# eMMCChip.net
KiCad netlist of a schematic drawn in Altium Designer
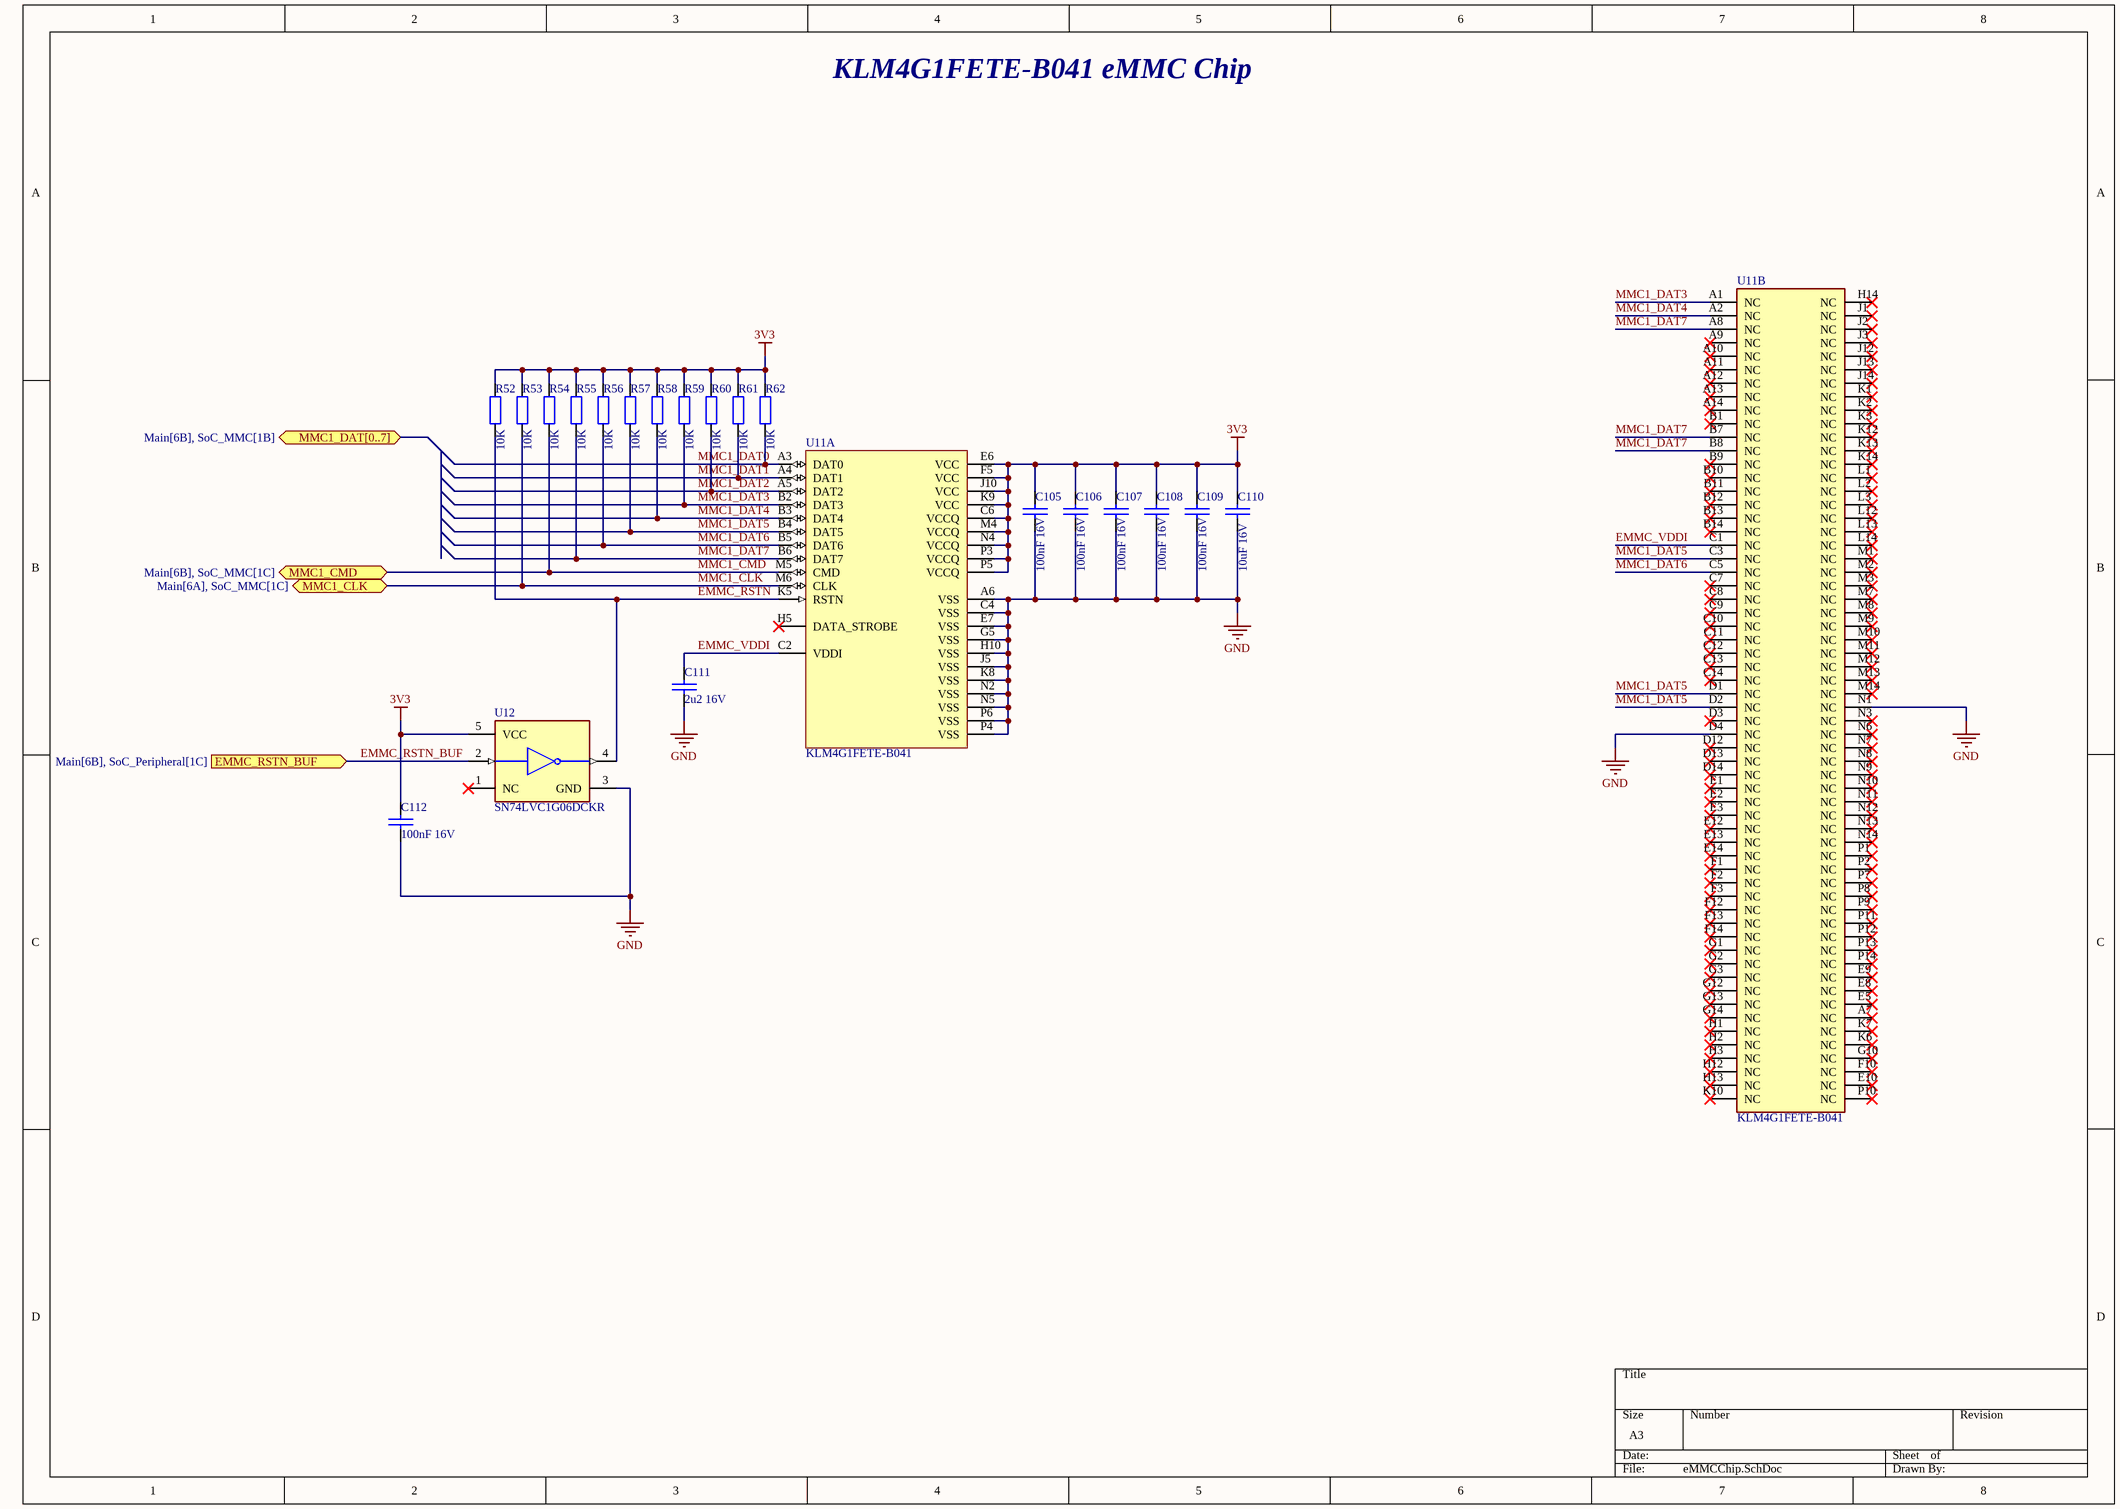
[diagram p0: eMMCChip.SchDoc]

(export (version "E")
  (design (tool "Eeschema 10.0.6"))
  (components
    (comp (ref "C105")
      (value "100nF 16V")
      (footprint "C_0402")
      (description "Capacitor 0402 SMD")
      (libsource (lib "tor1kkLib") (part "C_0402"))
    )
    (comp (ref "C106")
      (value "100nF 16V")
      (footprint "C_0402")
      (description "Capacitor 0402 SMD")
      (libsource (lib "tor1kkLib") (part "C_0402"))
    )
    (comp (ref "C107")
      (value "100nF 16V")
      (footprint "C_0402")
      (description "Capacitor 0402 SMD")
      (libsource (lib "tor1kkLib") (part "C_0402"))
    )
    (comp (ref "C108")
      (value "100nF 16V")
      (footprint "C_0402")
      (description "Capacitor 0402 SMD")
      (libsource (lib "tor1kkLib") (part "C_0402"))
    )
    (comp (ref "C109")
      (value "100nF 16V")
      (footprint "C_0402")
      (description "Capacitor 0402 SMD")
      (libsource (lib "tor1kkLib") (part "C_0402"))
    )
    (comp (ref "C110")
      (value "10uF 16V")
      (footprint "C_0603")
      (description "Capacitor 0603 SMD")
      (libsource (lib "tor1kkLib") (part "C_0603"))
    )
    (comp (ref "C111")
      (value "2u2 16V")
      (footprint "C_0402")
      (description "Capacitor 0402 SMD")
      (libsource (lib "tor1kkLib") (part "C_0402"))
    )
    (comp (ref "C112")
      (value "100nF 16V")
      (footprint "C_0402")
      (description "Capacitor 0402 SMD")
      (libsource (lib "tor1kkLib") (part "C_0402"))
    )
    (comp (ref "R52")
      (value "10K")
      (footprint "R_0402")
      (description "Resistor 0402 SMD")
      (libsource (lib "tor1kkLib") (part "R_0402"))
    )
    (comp (ref "R53")
      (value "10K")
      (footprint "R_0402")
      (description "Resistor 0402 SMD")
      (libsource (lib "tor1kkLib") (part "R_0402"))
    )
    (comp (ref "R54")
      (value "10K")
      (footprint "R_0402")
      (description "Resistor 0402 SMD")
      (libsource (lib "tor1kkLib") (part "R_0402"))
    )
    (comp (ref "R55")
      (value "10K")
      (footprint "R_0402")
      (description "Resistor 0402 SMD")
      (libsource (lib "tor1kkLib") (part "R_0402"))
    )
    (comp (ref "R56")
      (value "10K")
      (footprint "R_0402")
      (description "Resistor 0402 SMD")
      (libsource (lib "tor1kkLib") (part "R_0402"))
    )
    (comp (ref "R57")
      (value "10K")
      (footprint "R_0402")
      (description "Resistor 0402 SMD")
      (libsource (lib "tor1kkLib") (part "R_0402"))
    )
    (comp (ref "R58")
      (value "10K")
      (footprint "R_0402")
      (description "Resistor 0402 SMD")
      (libsource (lib "tor1kkLib") (part "R_0402"))
    )
    (comp (ref "R59")
      (value "10K")
      (footprint "R_0402")
      (description "Resistor 0402 SMD")
      (libsource (lib "tor1kkLib") (part "R_0402"))
    )
    (comp (ref "R60")
      (value "10K")
      (footprint "R_0402")
      (description "Resistor 0402 SMD")
      (libsource (lib "tor1kkLib") (part "R_0402"))
    )
    (comp (ref "R61")
      (value "10K")
      (footprint "R_0402")
      (description "Resistor 0402 SMD")
      (libsource (lib "tor1kkLib") (part "R_0402"))
    )
    (comp (ref "R62")
      (value "10K")
      (footprint "R_0402")
      (description "Resistor 0402 SMD")
      (libsource (lib "tor1kkLib") (part "R_0402"))
    )
    (comp (ref "U11")
      (value "KLM4G1FETE-B041")
      (footprint "BGA153C50P14X14_1100X1000X80")
      (description "4GB 300/19 MB/s eMMC 5.1 FBGA-153(10x11) eMMC ROHS")
      (fields (field (name "MANUFACTURER") "Samsung"))
      (libsource (lib "tor1kkLib") (part "KLM4G1FETE-B041"))
    )
    (comp (ref "U12")
      (value "SN74LVC1G06DCKR")
      (footprint "FP-DCK0005A-MFG")
      (description "IC BUFFER INVERT 5.5V SC70-5")
      (fields
        (field (name "MANUFACTURER") "Texas Instruments")
        (field (name "OCTOPART") "https://octopart.com/sn74lvc1g06dckr-texas+instruments-465505")
      )
      (libsource (lib "Altium Content Vault") (part "3c7ee7ed174875a000d335133ab233a"))
    )
  )
  (nets
    (net (code "1") (name "/EMMC_RSTN") (class "Default")
      (node (ref "R52") (pin "1") (pintype "passive"))
      (node (ref "U11") (pin "K5") (pinfunction "RSTN_K5") (pintype "input"))
      (node (ref "U12") (pin "4") (pinfunction "Y_4") (pintype "output"))
    )
    (net (code "2") (name "/EMMC_RSTN_BUF") (class "Default")
      (node (ref "U12") (pin "2") (pinfunction "A_2") (pintype "input"))
    )
    (net (code "3") (name "/EMMC_VDDI") (class "Default")
      (node (ref "C111") (pin "1") (pintype "passive"))
      (node (ref "U11") (pin "C1") (pinfunction "NC_C1") (pintype "passive"))
      (node (ref "U11") (pin "C2") (pinfunction "VDDI_C2") (pintype "passive"))
    )
    (net (code "4") (name "/MMC1_CLK") (class "Default")
      (node (ref "R53") (pin "1") (pintype "passive"))
      (node (ref "U11") (pin "M6") (pinfunction "CLK_M6") (pintype "bidirectional"))
    )
    (net (code "5") (name "/MMC1_CMD") (class "Default")
      (node (ref "R54") (pin "1") (pintype "passive"))
      (node (ref "U11") (pin "M5") (pinfunction "CMD_M5") (pintype "bidirectional"))
    )
    (net (code "6") (name "/MMC1_DAT0") (class "Default")
      (node (ref "R62") (pin "1") (pintype "passive"))
      (node (ref "U11") (pin "A3") (pinfunction "DAT0_A3") (pintype "bidirectional"))
    )
    (net (code "7") (name "/MMC1_DAT1") (class "Default")
      (node (ref "R61") (pin "1") (pintype "passive"))
      (node (ref "U11") (pin "A4") (pinfunction "DAT1_A4") (pintype "bidirectional"))
    )
    (net (code "8") (name "/MMC1_DAT2") (class "Default")
      (node (ref "R60") (pin "1") (pintype "passive"))
      (node (ref "U11") (pin "A5") (pinfunction "DAT2_A5") (pintype "bidirectional"))
    )
    (net (code "9") (name "/MMC1_DAT3") (class "Default")
      (node (ref "R59") (pin "1") (pintype "passive"))
      (node (ref "U11") (pin "A1") (pinfunction "NC_A1") (pintype "passive"))
      (node (ref "U11") (pin "B2") (pinfunction "DAT3_B2") (pintype "bidirectional"))
    )
    (net (code "10") (name "/MMC1_DAT4") (class "Default")
      (node (ref "R58") (pin "1") (pintype "passive"))
      (node (ref "U11") (pin "A2") (pinfunction "NC_A2") (pintype "passive"))
      (node (ref "U11") (pin "B3") (pinfunction "DAT4_B3") (pintype "bidirectional"))
    )
    (net (code "11") (name "/MMC1_DAT5") (class "Default")
      (node (ref "R57") (pin "1") (pintype "passive"))
      (node (ref "U11") (pin "B4") (pinfunction "DAT5_B4") (pintype "bidirectional"))
      (node (ref "U11") (pin "C3") (pinfunction "NC_C3") (pintype "passive"))
      (node (ref "U11") (pin "D1") (pinfunction "NC_D1") (pintype "passive"))
      (node (ref "U11") (pin "D2") (pinfunction "NC_D2") (pintype "passive"))
    )
    (net (code "12") (name "/MMC1_DAT6") (class "Default")
      (node (ref "R56") (pin "1") (pintype "passive"))
      (node (ref "U11") (pin "B5") (pinfunction "DAT6_B5") (pintype "bidirectional"))
      (node (ref "U11") (pin "C5") (pinfunction "NC_C5") (pintype "passive"))
    )
    (net (code "13") (name "/MMC1_DAT7") (class "Default")
      (node (ref "R55") (pin "1") (pintype "passive"))
      (node (ref "U11") (pin "A8") (pinfunction "NC_A8") (pintype "passive"))
      (node (ref "U11") (pin "B6") (pinfunction "DAT7_B6") (pintype "bidirectional"))
      (node (ref "U11") (pin "B7") (pinfunction "NC_B7") (pintype "passive"))
      (node (ref "U11") (pin "B8") (pinfunction "NC_B8") (pintype "passive"))
    )
    (net (code "15") (name "3V3") (class "Default")
      (node (ref "C105") (pin "1") (pintype "passive"))
      (node (ref "C106") (pin "1") (pintype "passive"))
      (node (ref "C107") (pin "1") (pintype "passive"))
      (node (ref "C108") (pin "1") (pintype "passive"))
      (node (ref "C109") (pin "1") (pintype "passive"))
      (node (ref "C110") (pin "1") (pintype "passive"))
      (node (ref "C112") (pin "1") (pintype "passive"))
      (node (ref "R52") (pin "2") (pintype "passive"))
      (node (ref "R53") (pin "2") (pintype "passive"))
      (node (ref "R54") (pin "2") (pintype "passive"))
      (node (ref "R55") (pin "2") (pintype "passive"))
      (node (ref "R56") (pin "2") (pintype "passive"))
      (node (ref "R57") (pin "2") (pintype "passive"))
      (node (ref "R58") (pin "2") (pintype "passive"))
      (node (ref "R59") (pin "2") (pintype "passive"))
      (node (ref "R60") (pin "2") (pintype "passive"))
      (node (ref "R61") (pin "2") (pintype "passive"))
      (node (ref "R62") (pin "2") (pintype "passive"))
      (node (ref "U11") (pin "C6") (pinfunction "VCCQ_C6") (pintype "passive"))
      (node (ref "U11") (pin "E6") (pinfunction "VCC_E6") (pintype "passive"))
      (node (ref "U11") (pin "F5") (pinfunction "VCC_F5") (pintype "passive"))
      (node (ref "U11") (pin "J10") (pinfunction "VCC_J10") (pintype "passive"))
      (node (ref "U11") (pin "K9") (pinfunction "VCC_K9") (pintype "passive"))
      (node (ref "U11") (pin "M4") (pinfunction "VCCQ_M4") (pintype "passive"))
      (node (ref "U11") (pin "N4") (pinfunction "VCCQ_N4") (pintype "passive"))
      (node (ref "U11") (pin "P3") (pinfunction "VCCQ_P3") (pintype "passive"))
      (node (ref "U11") (pin "P5") (pinfunction "VCCQ_P5") (pintype "passive"))
      (node (ref "U12") (pin "5") (pinfunction "VCC_5") (pintype "power_in"))
    )
    (net (code "16") (name "GND") (class "Default")
      (node (ref "C105") (pin "2") (pintype "passive"))
      (node (ref "C106") (pin "2") (pintype "passive"))
      (node (ref "C107") (pin "2") (pintype "passive"))
      (node (ref "C108") (pin "2") (pintype "passive"))
      (node (ref "C109") (pin "2") (pintype "passive"))
      (node (ref "C110") (pin "2") (pintype "passive"))
      (node (ref "C111") (pin "2") (pintype "passive"))
      (node (ref "C112") (pin "2") (pintype "passive"))
      (node (ref "U11") (pin "A6") (pinfunction "VSS_A6") (pintype "passive"))
      (node (ref "U11") (pin "C4") (pinfunction "VSS_C4") (pintype "passive"))
      (node (ref "U11") (pin "D4") (pinfunction "NC_D4") (pintype "passive"))
      (node (ref "U11") (pin "E7") (pinfunction "VSS_E7") (pintype "passive"))
      (node (ref "U11") (pin "G5") (pinfunction "VSS_G5") (pintype "passive"))
      (node (ref "U11") (pin "H10") (pinfunction "VSS_H10") (pintype "passive"))
      (node (ref "U11") (pin "J5") (pinfunction "VSS_J5") (pintype "passive"))
      (node (ref "U11") (pin "K8") (pinfunction "VSS_K8") (pintype "passive"))
      (node (ref "U11") (pin "N1") (pinfunction "NC_N1") (pintype "passive"))
      (node (ref "U11") (pin "N2") (pinfunction "VSS_N2") (pintype "passive"))
      (node (ref "U11") (pin "N5") (pinfunction "VSS_N5") (pintype "passive"))
      (node (ref "U11") (pin "P4") (pinfunction "VSS_P4") (pintype "passive"))
      (node (ref "U11") (pin "P6") (pinfunction "VSS_P6") (pintype "passive"))
      (node (ref "U12") (pin "3") (pinfunction "GND_3") (pintype "power_in"))
    )
    (net (code "17") (name "unconnected-(U11A-DATA_STROBE-PadH5)") (class "Default")
      (node (ref "U11") (pin "H5") (pinfunction "DATA_STROBE_H5") (pintype "passive+no_connect"))
    )
    (net (code "18") (name "unconnected-(U11B-NC-PadA7)") (class "Default")
      (node (ref "U11") (pin "A7") (pinfunction "NC_A7") (pintype "passive+no_connect"))
    )
    (net (code "19") (name "unconnected-(U11B-NC-PadA9)") (class "Default")
      (node (ref "U11") (pin "A9") (pinfunction "NC_A9") (pintype "passive+no_connect"))
    )
    (net (code "20") (name "unconnected-(U11B-NC-PadA10)") (class "Default")
      (node (ref "U11") (pin "A10") (pinfunction "NC_A10") (pintype "passive+no_connect"))
    )
    (net (code "21") (name "unconnected-(U11B-NC-PadA11)") (class "Default")
      (node (ref "U11") (pin "A11") (pinfunction "NC_A11") (pintype "passive+no_connect"))
    )
    (net (code "22") (name "unconnected-(U11B-NC-PadA12)") (class "Default")
      (node (ref "U11") (pin "A12") (pinfunction "NC_A12") (pintype "passive+no_connect"))
    )
    (net (code "23") (name "unconnected-(U11B-NC-PadA13)") (class "Default")
      (node (ref "U11") (pin "A13") (pinfunction "NC_A13") (pintype "passive+no_connect"))
    )
    (net (code "24") (name "unconnected-(U11B-NC-PadA14)") (class "Default")
      (node (ref "U11") (pin "A14") (pinfunction "NC_A14") (pintype "passive+no_connect"))
    )
    (net (code "25") (name "unconnected-(U11B-NC-PadB1)") (class "Default")
      (node (ref "U11") (pin "B1") (pinfunction "NC_B1") (pintype "passive+no_connect"))
    )
    (net (code "26") (name "unconnected-(U11B-NC-PadB9)") (class "Default")
      (node (ref "U11") (pin "B9") (pinfunction "NC_B9") (pintype "passive+no_connect"))
    )
    (net (code "27") (name "unconnected-(U11B-NC-PadB10)") (class "Default")
      (node (ref "U11") (pin "B10") (pinfunction "NC_B10") (pintype "passive+no_connect"))
    )
    (net (code "28") (name "unconnected-(U11B-NC-PadB11)") (class "Default")
      (node (ref "U11") (pin "B11") (pinfunction "NC_B11") (pintype "passive+no_connect"))
    )
    (net (code "29") (name "unconnected-(U11B-NC-PadB12)") (class "Default")
      (node (ref "U11") (pin "B12") (pinfunction "NC_B12") (pintype "passive+no_connect"))
    )
    (net (code "30") (name "unconnected-(U11B-NC-PadB13)") (class "Default")
      (node (ref "U11") (pin "B13") (pinfunction "NC_B13") (pintype "passive+no_connect"))
    )
    (net (code "31") (name "unconnected-(U11B-NC-PadB14)") (class "Default")
      (node (ref "U11") (pin "B14") (pinfunction "NC_B14") (pintype "passive+no_connect"))
    )
    (net (code "32") (name "unconnected-(U11B-NC-PadC7)") (class "Default")
      (node (ref "U11") (pin "C7") (pinfunction "NC_C7") (pintype "passive+no_connect"))
    )
    (net (code "33") (name "unconnected-(U11B-NC-PadC8)") (class "Default")
      (node (ref "U11") (pin "C8") (pinfunction "NC_C8") (pintype "passive+no_connect"))
    )
    (net (code "34") (name "unconnected-(U11B-NC-PadC9)") (class "Default")
      (node (ref "U11") (pin "C9") (pinfunction "NC_C9") (pintype "passive+no_connect"))
    )
    (net (code "35") (name "unconnected-(U11B-NC-PadC10)") (class "Default")
      (node (ref "U11") (pin "C10") (pinfunction "NC_C10") (pintype "passive+no_connect"))
    )
    (net (code "36") (name "unconnected-(U11B-NC-PadC11)") (class "Default")
      (node (ref "U11") (pin "C11") (pinfunction "NC_C11") (pintype "passive+no_connect"))
    )
    (net (code "37") (name "unconnected-(U11B-NC-PadC12)") (class "Default")
      (node (ref "U11") (pin "C12") (pinfunction "NC_C12") (pintype "passive+no_connect"))
    )
    (net (code "38") (name "unconnected-(U11B-NC-PadC13)") (class "Default")
      (node (ref "U11") (pin "C13") (pinfunction "NC_C13") (pintype "passive+no_connect"))
    )
    (net (code "39") (name "unconnected-(U11B-NC-PadC14)") (class "Default")
      (node (ref "U11") (pin "C14") (pinfunction "NC_C14") (pintype "passive+no_connect"))
    )
    (net (code "40") (name "unconnected-(U11B-NC-PadD3)") (class "Default")
      (node (ref "U11") (pin "D3") (pinfunction "NC_D3") (pintype "passive+no_connect"))
    )
    (net (code "41") (name "unconnected-(U11B-NC-PadD12)") (class "Default")
      (node (ref "U11") (pin "D12") (pinfunction "NC_D12") (pintype "passive+no_connect"))
    )
    (net (code "42") (name "unconnected-(U11B-NC-PadD13)") (class "Default")
      (node (ref "U11") (pin "D13") (pinfunction "NC_D13") (pintype "passive+no_connect"))
    )
    (net (code "43") (name "unconnected-(U11B-NC-PadD14)") (class "Default")
      (node (ref "U11") (pin "D14") (pinfunction "NC_D14") (pintype "passive+no_connect"))
    )
    (net (code "44") (name "unconnected-(U11B-NC-PadE1)") (class "Default")
      (node (ref "U11") (pin "E1") (pinfunction "NC_E1") (pintype "passive+no_connect"))
    )
    (net (code "45") (name "unconnected-(U11B-NC-PadE2)") (class "Default")
      (node (ref "U11") (pin "E2") (pinfunction "NC_E2") (pintype "passive+no_connect"))
    )
    (net (code "46") (name "unconnected-(U11B-NC-PadE3)") (class "Default")
      (node (ref "U11") (pin "E3") (pinfunction "NC_E3") (pintype "passive+no_connect"))
    )
    (net (code "47") (name "unconnected-(U11B-NC-PadE5)") (class "Default")
      (node (ref "U11") (pin "E5") (pinfunction "NC_E5") (pintype "passive+no_connect"))
    )
    (net (code "48") (name "unconnected-(U11B-NC-PadE8)") (class "Default")
      (node (ref "U11") (pin "E8") (pinfunction "NC_E8") (pintype "passive+no_connect"))
    )
    (net (code "49") (name "unconnected-(U11B-NC-PadE9)") (class "Default")
      (node (ref "U11") (pin "E9") (pinfunction "NC_E9") (pintype "passive+no_connect"))
    )
    (net (code "50") (name "unconnected-(U11B-NC-PadE10)") (class "Default")
      (node (ref "U11") (pin "E10") (pinfunction "NC_E10") (pintype "passive+no_connect"))
    )
    (net (code "51") (name "unconnected-(U11B-NC-PadE12)") (class "Default")
      (node (ref "U11") (pin "E12") (pinfunction "NC_E12") (pintype "passive+no_connect"))
    )
    (net (code "52") (name "unconnected-(U11B-NC-PadE13)") (class "Default")
      (node (ref "U11") (pin "E13") (pinfunction "NC_E13") (pintype "passive+no_connect"))
    )
    (net (code "53") (name "unconnected-(U11B-NC-PadE14)") (class "Default")
      (node (ref "U11") (pin "E14") (pinfunction "NC_E14") (pintype "passive+no_connect"))
    )
    (net (code "54") (name "unconnected-(U11B-NC-PadF1)") (class "Default")
      (node (ref "U11") (pin "F1") (pinfunction "NC_F1") (pintype "passive+no_connect"))
    )
    (net (code "55") (name "unconnected-(U11B-NC-PadF2)") (class "Default")
      (node (ref "U11") (pin "F2") (pinfunction "NC_F2") (pintype "passive+no_connect"))
    )
    (net (code "56") (name "unconnected-(U11B-NC-PadF3)") (class "Default")
      (node (ref "U11") (pin "F3") (pinfunction "NC_F3") (pintype "passive+no_connect"))
    )
    (net (code "57") (name "unconnected-(U11B-NC-PadF10)") (class "Default")
      (node (ref "U11") (pin "F10") (pinfunction "NC_F10") (pintype "passive+no_connect"))
    )
    (net (code "58") (name "unconnected-(U11B-NC-PadF12)") (class "Default")
      (node (ref "U11") (pin "F12") (pinfunction "NC_F12") (pintype "passive+no_connect"))
    )
    (net (code "59") (name "unconnected-(U11B-NC-PadF13)") (class "Default")
      (node (ref "U11") (pin "F13") (pinfunction "NC_F13") (pintype "passive+no_connect"))
    )
    (net (code "60") (name "unconnected-(U11B-NC-PadF14)") (class "Default")
      (node (ref "U11") (pin "F14") (pinfunction "NC_F14") (pintype "passive+no_connect"))
    )
    (net (code "61") (name "unconnected-(U11B-NC-PadG1)") (class "Default")
      (node (ref "U11") (pin "G1") (pinfunction "NC_G1") (pintype "passive+no_connect"))
    )
    (net (code "62") (name "unconnected-(U11B-NC-PadG2)") (class "Default")
      (node (ref "U11") (pin "G2") (pinfunction "NC_G2") (pintype "passive+no_connect"))
    )
    (net (code "63") (name "unconnected-(U11B-NC-PadG3)") (class "Default")
      (node (ref "U11") (pin "G3") (pinfunction "NC_G3") (pintype "passive+no_connect"))
    )
    (net (code "64") (name "unconnected-(U11B-NC-PadG10)") (class "Default")
      (node (ref "U11") (pin "G10") (pinfunction "NC_G10") (pintype "passive+no_connect"))
    )
    (net (code "65") (name "unconnected-(U11B-NC-PadG12)") (class "Default")
      (node (ref "U11") (pin "G12") (pinfunction "NC_G12") (pintype "passive+no_connect"))
    )
    (net (code "66") (name "unconnected-(U11B-NC-PadG13)") (class "Default")
      (node (ref "U11") (pin "G13") (pinfunction "NC_G13") (pintype "passive+no_connect"))
    )
    (net (code "67") (name "unconnected-(U11B-NC-PadG14)") (class "Default")
      (node (ref "U11") (pin "G14") (pinfunction "NC_G14") (pintype "passive+no_connect"))
    )
    (net (code "68") (name "unconnected-(U11B-NC-PadH1)") (class "Default")
      (node (ref "U11") (pin "H1") (pinfunction "NC_H1") (pintype "passive+no_connect"))
    )
    (net (code "69") (name "unconnected-(U11B-NC-PadH2)") (class "Default")
      (node (ref "U11") (pin "H2") (pinfunction "NC_H2") (pintype "passive+no_connect"))
    )
    (net (code "70") (name "unconnected-(U11B-NC-PadH3)") (class "Default")
      (node (ref "U11") (pin "H3") (pinfunction "NC_H3") (pintype "passive+no_connect"))
    )
    (net (code "71") (name "unconnected-(U11B-NC-PadH12)") (class "Default")
      (node (ref "U11") (pin "H12") (pinfunction "NC_H12") (pintype "passive+no_connect"))
    )
    (net (code "72") (name "unconnected-(U11B-NC-PadH13)") (class "Default")
      (node (ref "U11") (pin "H13") (pinfunction "NC_H13") (pintype "passive+no_connect"))
    )
    (net (code "73") (name "unconnected-(U11B-NC-PadH14)") (class "Default")
      (node (ref "U11") (pin "H14") (pinfunction "NC_H14") (pintype "passive+no_connect"))
    )
    (net (code "74") (name "unconnected-(U11B-NC-PadJ1)") (class "Default")
      (node (ref "U11") (pin "J1") (pinfunction "NC_J1") (pintype "passive+no_connect"))
    )
    (net (code "75") (name "unconnected-(U11B-NC-PadJ2)") (class "Default")
      (node (ref "U11") (pin "J2") (pinfunction "NC_J2") (pintype "passive+no_connect"))
    )
    (net (code "76") (name "unconnected-(U11B-NC-PadJ3)") (class "Default")
      (node (ref "U11") (pin "J3") (pinfunction "NC_J3") (pintype "passive+no_connect"))
    )
    (net (code "77") (name "unconnected-(U11B-NC-PadJ12)") (class "Default")
      (node (ref "U11") (pin "J12") (pinfunction "NC_J12") (pintype "passive+no_connect"))
    )
    (net (code "78") (name "unconnected-(U11B-NC-PadJ13)") (class "Default")
      (node (ref "U11") (pin "J13") (pinfunction "NC_J13") (pintype "passive+no_connect"))
    )
    (net (code "79") (name "unconnected-(U11B-NC-PadJ14)") (class "Default")
      (node (ref "U11") (pin "J14") (pinfunction "NC_J14") (pintype "passive+no_connect"))
    )
    (net (code "80") (name "unconnected-(U11B-NC-PadK1)") (class "Default")
      (node (ref "U11") (pin "K1") (pinfunction "NC_K1") (pintype "passive+no_connect"))
    )
    (net (code "81") (name "unconnected-(U11B-NC-PadK2)") (class "Default")
      (node (ref "U11") (pin "K2") (pinfunction "NC_K2") (pintype "passive+no_connect"))
    )
    (net (code "82") (name "unconnected-(U11B-NC-PadK3)") (class "Default")
      (node (ref "U11") (pin "K3") (pinfunction "NC_K3") (pintype "passive+no_connect"))
    )
    (net (code "83") (name "unconnected-(U11B-NC-PadK6)") (class "Default")
      (node (ref "U11") (pin "K6") (pinfunction "NC_K6") (pintype "passive+no_connect"))
    )
    (net (code "84") (name "unconnected-(U11B-NC-PadK7)") (class "Default")
      (node (ref "U11") (pin "K7") (pinfunction "NC_K7") (pintype "passive+no_connect"))
    )
    (net (code "85") (name "unconnected-(U11B-NC-PadK10)") (class "Default")
      (node (ref "U11") (pin "K10") (pinfunction "NC_K10") (pintype "passive+no_connect"))
    )
    (net (code "86") (name "unconnected-(U11B-NC-PadK12)") (class "Default")
      (node (ref "U11") (pin "K12") (pinfunction "NC_K12") (pintype "passive+no_connect"))
    )
    (net (code "87") (name "unconnected-(U11B-NC-PadK13)") (class "Default")
      (node (ref "U11") (pin "K13") (pinfunction "NC_K13") (pintype "passive+no_connect"))
    )
    (net (code "88") (name "unconnected-(U11B-NC-PadK14)") (class "Default")
      (node (ref "U11") (pin "K14") (pinfunction "NC_K14") (pintype "passive+no_connect"))
    )
    (net (code "89") (name "unconnected-(U11B-NC-PadL1)") (class "Default")
      (node (ref "U11") (pin "L1") (pinfunction "NC_L1") (pintype "passive+no_connect"))
    )
    (net (code "90") (name "unconnected-(U11B-NC-PadL2)") (class "Default")
      (node (ref "U11") (pin "L2") (pinfunction "NC_L2") (pintype "passive+no_connect"))
    )
    (net (code "91") (name "unconnected-(U11B-NC-PadL3)") (class "Default")
      (node (ref "U11") (pin "L3") (pinfunction "NC_L3") (pintype "passive+no_connect"))
    )
    (net (code "92") (name "unconnected-(U11B-NC-PadL12)") (class "Default")
      (node (ref "U11") (pin "L12") (pinfunction "NC_L12") (pintype "passive+no_connect"))
    )
    (net (code "93") (name "unconnected-(U11B-NC-PadL13)") (class "Default")
      (node (ref "U11") (pin "L13") (pinfunction "NC_L13") (pintype "passive+no_connect"))
    )
    (net (code "94") (name "unconnected-(U11B-NC-PadL14)") (class "Default")
      (node (ref "U11") (pin "L14") (pinfunction "NC_L14") (pintype "passive+no_connect"))
    )
    (net (code "95") (name "unconnected-(U11B-NC-PadM1)") (class "Default")
      (node (ref "U11") (pin "M1") (pinfunction "NC_M1") (pintype "passive+no_connect"))
    )
    (net (code "96") (name "unconnected-(U11B-NC-PadM2)") (class "Default")
      (node (ref "U11") (pin "M2") (pinfunction "NC_M2") (pintype "passive+no_connect"))
    )
    (net (code "97") (name "unconnected-(U11B-NC-PadM3)") (class "Default")
      (node (ref "U11") (pin "M3") (pinfunction "NC_M3") (pintype "passive+no_connect"))
    )
    (net (code "98") (name "unconnected-(U11B-NC-PadM7)") (class "Default")
      (node (ref "U11") (pin "M7") (pinfunction "NC_M7") (pintype "passive+no_connect"))
    )
    (net (code "99") (name "unconnected-(U11B-NC-PadM8)") (class "Default")
      (node (ref "U11") (pin "M8") (pinfunction "NC_M8") (pintype "passive+no_connect"))
    )
    (net (code "100") (name "unconnected-(U11B-NC-PadM9)") (class "Default")
      (node (ref "U11") (pin "M9") (pinfunction "NC_M9") (pintype "passive+no_connect"))
    )
    (net (code "101") (name "unconnected-(U11B-NC-PadM10)") (class "Default")
      (node (ref "U11") (pin "M10") (pinfunction "NC_M10") (pintype "passive+no_connect"))
    )
    (net (code "102") (name "unconnected-(U11B-NC-PadM11)") (class "Default")
      (node (ref "U11") (pin "M11") (pinfunction "NC_M11") (pintype "passive+no_connect"))
    )
    (net (code "103") (name "unconnected-(U11B-NC-PadM12)") (class "Default")
      (node (ref "U11") (pin "M12") (pinfunction "NC_M12") (pintype "passive+no_connect"))
    )
    (net (code "104") (name "unconnected-(U11B-NC-PadM13)") (class "Default")
      (node (ref "U11") (pin "M13") (pinfunction "NC_M13") (pintype "passive+no_connect"))
    )
    (net (code "105") (name "unconnected-(U11B-NC-PadM14)") (class "Default")
      (node (ref "U11") (pin "M14") (pinfunction "NC_M14") (pintype "passive+no_connect"))
    )
    (net (code "106") (name "unconnected-(U11B-NC-PadN3)") (class "Default")
      (node (ref "U11") (pin "N3") (pinfunction "NC_N3") (pintype "passive+no_connect"))
    )
    (net (code "107") (name "unconnected-(U11B-NC-PadN6)") (class "Default")
      (node (ref "U11") (pin "N6") (pinfunction "NC_N6") (pintype "passive+no_connect"))
    )
    (net (code "108") (name "unconnected-(U11B-NC-PadN7)") (class "Default")
      (node (ref "U11") (pin "N7") (pinfunction "NC_N7") (pintype "passive+no_connect"))
    )
    (net (code "109") (name "unconnected-(U11B-NC-PadN8)") (class "Default")
      (node (ref "U11") (pin "N8") (pinfunction "NC_N8") (pintype "passive+no_connect"))
    )
    (net (code "110") (name "unconnected-(U11B-NC-PadN9)") (class "Default")
      (node (ref "U11") (pin "N9") (pinfunction "NC_N9") (pintype "passive+no_connect"))
    )
    (net (code "111") (name "unconnected-(U11B-NC-PadN10)") (class "Default")
      (node (ref "U11") (pin "N10") (pinfunction "NC_N10") (pintype "passive+no_connect"))
    )
    (net (code "112") (name "unconnected-(U11B-NC-PadN11)") (class "Default")
      (node (ref "U11") (pin "N11") (pinfunction "NC_N11") (pintype "passive+no_connect"))
    )
    (net (code "113") (name "unconnected-(U11B-NC-PadN12)") (class "Default")
      (node (ref "U11") (pin "N12") (pinfunction "NC_N12") (pintype "passive+no_connect"))
    )
    (net (code "114") (name "unconnected-(U11B-NC-PadN13)") (class "Default")
      (node (ref "U11") (pin "N13") (pinfunction "NC_N13") (pintype "passive+no_connect"))
    )
    (net (code "115") (name "unconnected-(U11B-NC-PadN14)") (class "Default")
      (node (ref "U11") (pin "N14") (pinfunction "NC_N14") (pintype "passive+no_connect"))
    )
    (net (code "116") (name "unconnected-(U11B-NC-PadP1)") (class "Default")
      (node (ref "U11") (pin "P1") (pinfunction "NC_P1") (pintype "passive+no_connect"))
    )
    (net (code "117") (name "unconnected-(U11B-NC-PadP2)") (class "Default")
      (node (ref "U11") (pin "P2") (pinfunction "NC_P2") (pintype "passive+no_connect"))
    )
    (net (code "118") (name "unconnected-(U11B-NC-PadP7)") (class "Default")
      (node (ref "U11") (pin "P7") (pinfunction "NC_P7") (pintype "passive+no_connect"))
    )
    (net (code "119") (name "unconnected-(U11B-NC-PadP8)") (class "Default")
      (node (ref "U11") (pin "P8") (pinfunction "NC_P8") (pintype "passive+no_connect"))
    )
    (net (code "120") (name "unconnected-(U11B-NC-PadP9)") (class "Default")
      (node (ref "U11") (pin "P9") (pinfunction "NC_P9") (pintype "passive+no_connect"))
    )
    (net (code "121") (name "unconnected-(U11B-NC-PadP10)") (class "Default")
      (node (ref "U11") (pin "P10") (pinfunction "NC_P10") (pintype "passive+no_connect"))
    )
    (net (code "122") (name "unconnected-(U11B-NC-PadP11)") (class "Default")
      (node (ref "U11") (pin "P11") (pinfunction "NC_P11") (pintype "passive+no_connect"))
    )
    (net (code "123") (name "unconnected-(U11B-NC-PadP12)") (class "Default")
      (node (ref "U11") (pin "P12") (pinfunction "NC_P12") (pintype "passive+no_connect"))
    )
    (net (code "124") (name "unconnected-(U11B-NC-PadP13)") (class "Default")
      (node (ref "U11") (pin "P13") (pinfunction "NC_P13") (pintype "passive+no_connect"))
    )
    (net (code "125") (name "unconnected-(U11B-NC-PadP14)") (class "Default")
      (node (ref "U11") (pin "P14") (pinfunction "NC_P14") (pintype "passive+no_connect"))
    )
    (net (code "126") (name "unconnected-(U12-NC-Pad1)") (class "Default")
      (node (ref "U12") (pin "1") (pinfunction "NC_1") (pintype "passive+no_connect"))
    )
  )
)
